# only_converter.net
KiCad netlist of a schematic drawn in Altium Designer
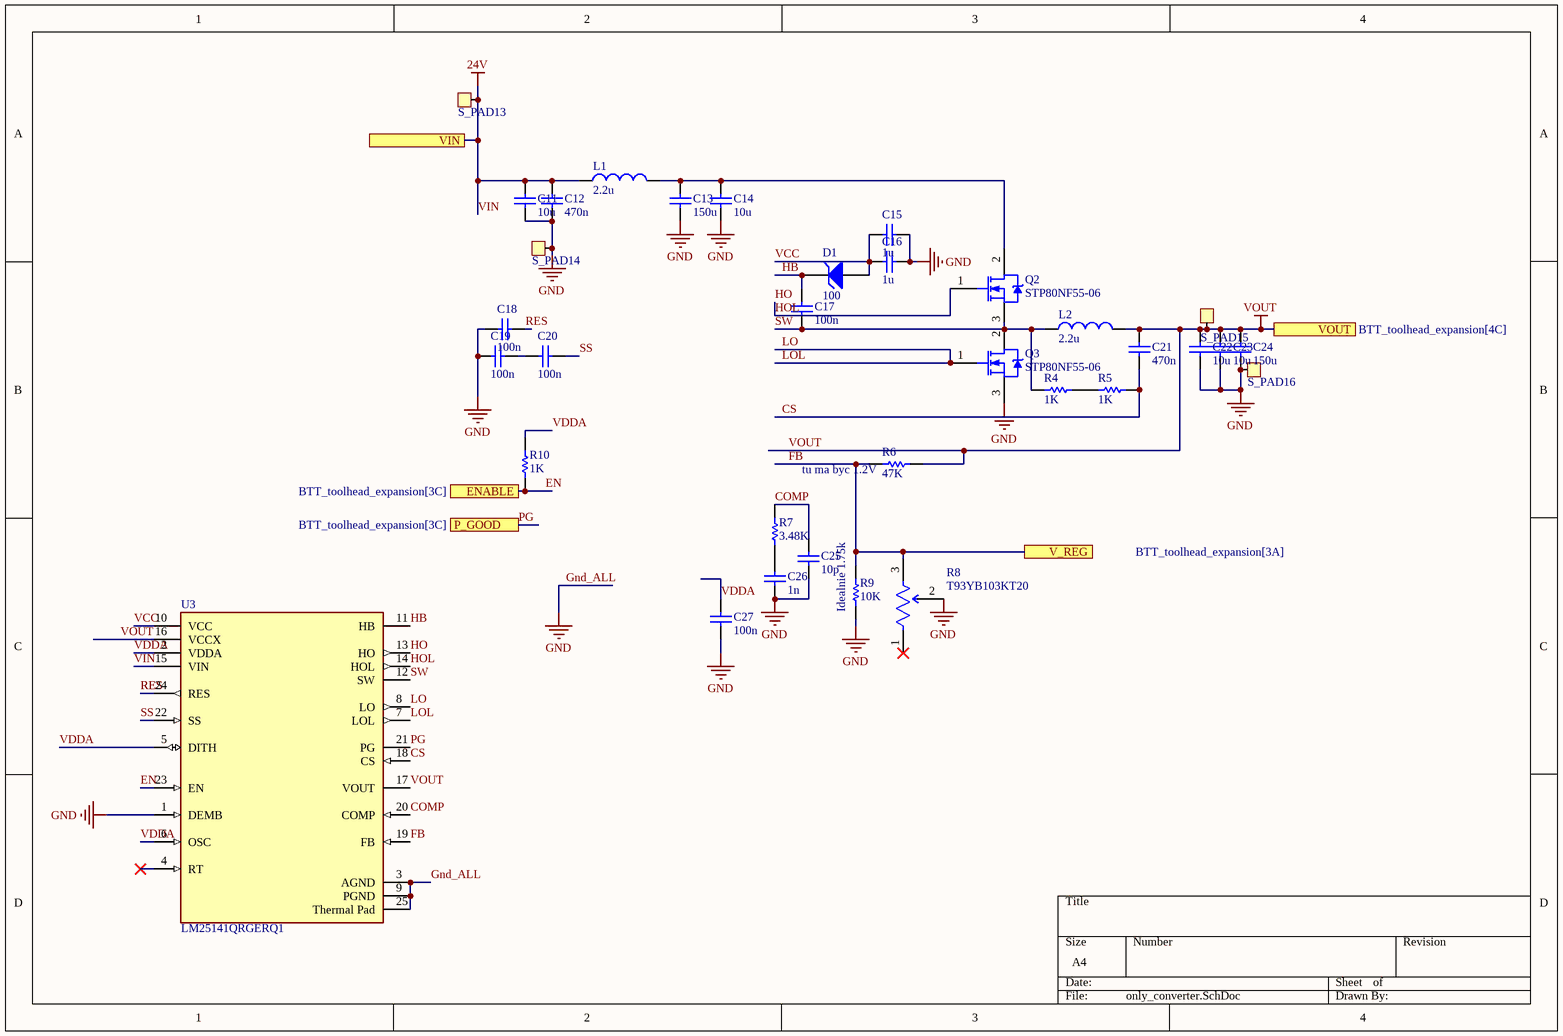
[diagram p0: only_converter.SchDoc]

(export (version "E")
  (design (tool "Eeschema 10.0.6"))
  (components
    (comp (ref "C11")
      (value "10u")
      (footprint "CAP FILM 0805")
      (description "Daj tu ten wiekszy 0805 dzbanie")
      (fields (field (name "Comment") "Capacitor"))
      (libsource (lib "Simulation Generic Components") (part "Capacitor"))
    )
    (comp (ref "C12")
      (value "470n")
      (footprint "CAP FILM 0603_1608")
      (description "Capacitor")
      (libsource (lib "Simulation Generic Components") (part "Capacitor"))
    )
    (comp (ref "C13")
      (value "150u")
      (footprint "CAPAE7266X80M")
      (description "to ten duzy elektrolityczny smd")
      (fields (field (name "Comment") "Capacitor"))
      (libsource (lib "Simulation Generic Components") (part "Capacitor"))
    )
    (comp (ref "C14")
      (value "10u")
      (footprint "CAP FILM 0805")
      (description "Daj tu ten wiekszy 0805 dzbanie")
      (fields (field (name "Comment") "Capacitor"))
      (libsource (lib "Simulation Generic Components") (part "Capacitor"))
    )
    (comp (ref "C15")
      (value "1u")
      (footprint "CAP FILM 0603_1608")
      (description "Capacitor")
      (libsource (lib "Simulation Generic Components") (part "Capacitor"))
    )
    (comp (ref "C16")
      (value "1u")
      (footprint "CAP FILM 0603_1608")
      (description "Capacitor")
      (libsource (lib "Simulation Generic Components") (part "Capacitor"))
    )
    (comp (ref "C17")
      (value "100n")
      (footprint "CAP FILM 0603_1608")
      (description "Capacitor")
      (libsource (lib "Simulation Generic Components") (part "Capacitor"))
    )
    (comp (ref "C18")
      (value "100n")
      (footprint "CAP FILM 0603_1608")
      (description "Capacitor")
      (libsource (lib "Simulation Generic Components") (part "Capacitor"))
    )
    (comp (ref "C19")
      (value "100n")
      (footprint "CAP FILM 0603_1608")
      (description "Capacitor")
      (libsource (lib "Simulation Generic Components") (part "Capacitor"))
    )
    (comp (ref "C20")
      (value "100n")
      (footprint "CAP FILM 0603_1608")
      (description "Capacitor")
      (libsource (lib "Simulation Generic Components") (part "Capacitor"))
    )
    (comp (ref "C21")
      (value "470n")
      (footprint "CAP FILM 0603_1608")
      (description "Capacitor")
      (libsource (lib "Simulation Generic Components") (part "Capacitor"))
    )
    (comp (ref "C22")
      (value "10u")
      (footprint "CAP FILM 0603_1608")
      (description "Daj tu ten wiekszy 0805 dzbanie")
      (fields (field (name "Comment") "Capacitor"))
      (libsource (lib "Simulation Generic Components") (part "Capacitor"))
    )
    (comp (ref "C23")
      (value "10u")
      (footprint "CAP FILM 0603_1608")
      (description "Daj tu ten wiekszy 0805 dzbanie")
      (fields (field (name "Comment") "Capacitor"))
      (libsource (lib "Simulation Generic Components") (part "Capacitor"))
    )
    (comp (ref "C24")
      (value "150u")
      (footprint "CAPAE7266X80M")
      (description "to ten duzy elektrolityczny smd")
      (fields (field (name "Comment") "Capacitor"))
      (libsource (lib "Simulation Generic Components") (part "Capacitor"))
    )
    (comp (ref "C25")
      (value "10p")
      (footprint "CAP FILM 0603_1608")
      (description "Capacitor")
      (libsource (lib "Simulation Generic Components") (part "Capacitor"))
    )
    (comp (ref "C26")
      (value "1n")
      (footprint "CAP FILM 0603_1608")
      (description "Capacitor")
      (libsource (lib "Simulation Generic Components") (part "Capacitor"))
    )
    (comp (ref "C27")
      (value "100n")
      (footprint "CAP FILM 0603_1608")
      (description "Capacitor")
      (libsource (lib "Simulation Generic Components") (part "Capacitor"))
    )
    (comp (ref "D1")
      (value "Zener Diode")
      (footprint "SODFL375X135-2N")
      (fields (field (name "BV") "100"))
      (libsource (lib "Simulation Generic Components") (part "Zener Diode"))
    )
    (comp (ref "L1")
      (value "2.2u")
      (footprint "INDP135128X65N")
      (description "Inductor")
      (libsource (lib "Simulation Generic Components") (part "Inductor"))
    )
    (comp (ref "L2")
      (value "2.2u")
      (footprint "INDP135128X65N")
      (description "Inductor")
      (libsource (lib "Simulation Generic Components") (part "Inductor"))
    )
    (comp (ref "Q2")
      (value "STP80NF55-06")
      (footprint "STM-TO-220A-3")
      (fields (field (name "MANUFACTURER") "STMicroelectronics"))
      (libsource (lib "Altium Content Vault") (part "NEMOS-GDS-3_B"))
    )
    (comp (ref "Q3")
      (value "STP80NF55-06")
      (footprint "STM-TO-220A-3")
      (fields (field (name "MANUFACTURER") "STMicroelectronics"))
      (libsource (lib "Altium Content Vault") (part "NEMOS-GDS-3_B"))
    )
    (comp (ref "R4")
      (value "1K")
      (footprint "RES 0603_1608")
      (description "Resistor")
      (libsource (lib "Simulation Generic Components") (part "Resistor"))
    )
    (comp (ref "R5")
      (value "1K")
      (footprint "RES 0603_1608")
      (description "Resistor")
      (libsource (lib "Simulation Generic Components") (part "Resistor"))
    )
    (comp (ref "R6")
      (value "47K")
      (footprint "RES 0603_1608")
      (description "Resistor")
      (libsource (lib "Simulation Generic Components") (part "Resistor"))
    )
    (comp (ref "R7")
      (value "3.48K")
      (footprint "RES 0603_1608")
      (description "Resistor")
      (libsource (lib "Simulation Generic Components") (part "Resistor"))
    )
    (comp (ref "R8")
      (value "T93YB103KT20")
      (footprint "FP-T93YB-MFG")
      (description "T93YB103KT20 Resistor Trimmer, Cermet, 10 kOhm, ± 10%, 500 mW, 23 Turn, Multi Turn, Through Hole")
      (fields (field (name "TOLERANCE") "10%"))
      (libsource (lib "Altium Content Vault") (part "af6d6fb613c1f66b9b47f3e4c9350cb"))
    )
    (comp (ref "R9")
      (value "10K")
      (footprint "RES 0603_1608")
      (description "Resistor")
      (libsource (lib "Simulation Generic Components") (part "Resistor"))
    )
    (comp (ref "R10")
      (value "1K")
      (footprint "RES 0603_1608 RF")
      (description "Resistor")
      (libsource (lib "Simulation Generic Components") (part "Resistor"))
    )
    (comp (ref "S_PAD13")
      (value "SOLDER_PAD")
      (footprint "POWER_PAD")
      (libsource (lib "") (part "SOLDER_PAD_1"))
    )
    (comp (ref "S_PAD14")
      (value "SOLDER_PAD")
      (footprint "POWER_PAD")
      (libsource (lib "") (part "SOLDER_PAD_2"))
    )
    (comp (ref "S_PAD15")
      (value "SOLDER_PAD")
      (footprint "POWER_PAD")
      (libsource (lib "") (part "SOLDER_PAD_3"))
    )
    (comp (ref "S_PAD16")
      (value "SOLDER_PAD")
      (footprint "POWER_PAD")
      (libsource (lib "solderpad") (part "SOLDER_PAD"))
    )
    (comp (ref "U3")
      (value "LM25141QRGERQ1")
      (footprint "FP-RGE0024J-IPC_A")
      (description "AUTOMOTIVE, 2.2MHZ, LOW IQ SYNCH")
      (libsource (lib "Altium Content Vault") (part "c442b2b45abbae5fb835a6b35668121"))
    )
  )
  (nets
    (net (code "1") (name "/COMP") (class "Default")
      (node (ref "C25") (pin "2") (pinfunction "2_2") (pintype "passive"))
      (node (ref "R7") (pin "2") (pinfunction "2_2") (pintype "passive"))
      (node (ref "U3") (pin "20") (pinfunction "COMP_20") (pintype "input"))
    )
    (net (code "2") (name "/CS") (class "Default")
      (node (ref "C21") (pin "1") (pinfunction "1_1") (pintype "passive"))
      (node (ref "R5") (pin "2") (pinfunction "2_2") (pintype "passive"))
      (node (ref "U3") (pin "18") (pinfunction "CS_18") (pintype "input"))
    )
    (net (code "3") (name "/EN") (class "Default")
      (node (ref "R10") (pin "1") (pinfunction "1_1") (pintype "passive"))
      (node (ref "U3") (pin "23") (pinfunction "EN_23") (pintype "input"))
    )
    (net (code "4") (name "/FB") (class "Default")
      (node (ref "R6") (pin "1") (pinfunction "1_1") (pintype "passive"))
      (node (ref "R8") (pin "3") (pinfunction "c_3") (pintype "passive"))
      (node (ref "R9") (pin "2") (pinfunction "2_2") (pintype "passive"))
      (node (ref "U3") (pin "19") (pinfunction "FB_19") (pintype "input"))
    )
    (net (code "5") (name "/HB") (class "Default")
      (node (ref "C17") (pin "2") (pinfunction "2_2") (pintype "passive"))
      (node (ref "D1") (pin "2") (pinfunction "K_2") (pintype "passive"))
      (node (ref "U3") (pin "11") (pinfunction "HB_11") (pintype "power_in"))
    )
    (net (code "6") (name "/HO") (class "Default")
      (node (ref "Q2") (pin "1") (pinfunction "G_1") (pintype "passive"))
      (node (ref "U3") (pin "13") (pinfunction "HO_13") (pintype "output"))
      (node (ref "U3") (pin "14") (pinfunction "HOL_14") (pintype "output"))
    )
    (net (code "7") (name "/LO") (class "Default")
      (node (ref "Q3") (pin "1") (pinfunction "G_1") (pintype "passive"))
      (node (ref "U3") (pin "7") (pinfunction "LOL_7") (pintype "output"))
      (node (ref "U3") (pin "8") (pinfunction "LO_8") (pintype "output"))
    )
    (net (code "8") (name "/PG") (class "Default")
      (node (ref "U3") (pin "21") (pinfunction "PG_21") (pintype "open_collector"))
    )
    (net (code "9") (name "/RES") (class "Default")
      (node (ref "C18") (pin "2") (pinfunction "2_2") (pintype "passive"))
      (node (ref "U3") (pin "24") (pinfunction "RES_24") (pintype "output"))
    )
    (net (code "10") (name "/SS") (class "Default")
      (node (ref "C20") (pin "2") (pinfunction "2_2") (pintype "passive"))
      (node (ref "U3") (pin "22") (pinfunction "SS_22") (pintype "input"))
    )
    (net (code "11") (name "/SW") (class "Default")
      (node (ref "C17") (pin "1") (pinfunction "1_1") (pintype "passive"))
      (node (ref "L2") (pin "1") (pinfunction "1_1") (pintype "passive"))
      (node (ref "Q2") (pin "3") (pinfunction "S_3") (pintype "passive"))
      (node (ref "Q3") (pin "2") (pinfunction "D_2") (pintype "passive"))
      (node (ref "R4") (pin "1") (pinfunction "1_1") (pintype "passive"))
      (node (ref "U3") (pin "12") (pinfunction "SW_12") (pintype "power_in"))
    )
    (net (code "12") (name "/VCC") (class "Default")
      (node (ref "C15") (pin "2") (pinfunction "2_2") (pintype "passive"))
      (node (ref "C16") (pin "2") (pinfunction "2_2") (pintype "passive"))
      (node (ref "D1") (pin "1") (pinfunction "A_1") (pintype "passive"))
      (node (ref "U3") (pin "10") (pinfunction "VCC_10") (pintype "power_in"))
    )
    (net (code "13") (name "/VDDA") (class "Default")
      (node (ref "C27") (pin "2") (pinfunction "2_2") (pintype "passive"))
      (node (ref "R10") (pin "2") (pinfunction "2_2") (pintype "passive"))
      (node (ref "U3") (pin "2") (pinfunction "VDDA_2") (pintype "power_in"))
      (node (ref "U3") (pin "5") (pinfunction "DITH_5") (pintype "bidirectional"))
      (node (ref "U3") (pin "6") (pinfunction "OSC_6") (pintype "input"))
    )
    (net (code "14") (name "24V") (class "Default")
      (node (ref "C11") (pin "2") (pinfunction "2_2") (pintype "passive"))
      (node (ref "C12") (pin "2") (pinfunction "2_2") (pintype "passive"))
      (node (ref "L1") (pin "1") (pinfunction "1_1") (pintype "passive"))
      (node (ref "S_PAD13") (pin "1") (pinfunction "0_1") (pintype "passive"))
      (node (ref "U3") (pin "15") (pinfunction "VIN_15") (pintype "power_in"))
    )
    (net (code "15") (name "GND") (class "Default")
      (node (ref "C11") (pin "1") (pinfunction "1_1") (pintype "passive"))
      (node (ref "C12") (pin "1") (pinfunction "1_1") (pintype "passive"))
      (node (ref "C13") (pin "1") (pinfunction "1_1") (pintype "passive"))
      (node (ref "C14") (pin "1") (pinfunction "1_1") (pintype "passive"))
      (node (ref "C15") (pin "1") (pinfunction "1_1") (pintype "passive"))
      (node (ref "C16") (pin "1") (pinfunction "1_1") (pintype "passive"))
      (node (ref "C18") (pin "1") (pinfunction "1_1") (pintype "passive"))
      (node (ref "C19") (pin "1") (pinfunction "1_1") (pintype "passive"))
      (node (ref "C22") (pin "1") (pinfunction "1_1") (pintype "passive"))
      (node (ref "C23") (pin "1") (pinfunction "1_1") (pintype "passive"))
      (node (ref "C24") (pin "1") (pinfunction "1_1") (pintype "passive"))
      (node (ref "C25") (pin "1") (pinfunction "1_1") (pintype "passive"))
      (node (ref "C26") (pin "1") (pinfunction "1_1") (pintype "passive"))
      (node (ref "C27") (pin "1") (pinfunction "1_1") (pintype "passive"))
      (node (ref "Q3") (pin "3") (pinfunction "S_3") (pintype "passive"))
      (node (ref "R8") (pin "2") (pinfunction "b_2") (pintype "passive"))
      (node (ref "R9") (pin "1") (pinfunction "1_1") (pintype "passive"))
      (node (ref "S_PAD14") (pin "1") (pinfunction "0_1") (pintype "passive"))
      (node (ref "S_PAD16") (pin "1") (pinfunction "0_1") (pintype "passive"))
      (node (ref "U3") (pin "1") (pinfunction "DEMB_1") (pintype "input"))
      (node (ref "U3") (pin "25") (pinfunction "Thermal_Pad_25") (pintype "power_in"))
      (node (ref "U3") (pin "3") (pinfunction "AGND_3") (pintype "power_in"))
      (node (ref "U3") (pin "9") (pinfunction "PGND_9") (pintype "power_in"))
    )
    (net (code "16") (name "Net-(C19-Pad2)") (class "Default")
      (node (ref "C19") (pin "2") (pinfunction "2_2") (pintype "passive"))
      (node (ref "C20") (pin "1") (pinfunction "1_1") (pintype "passive"))
    )
    (net (code "17") (name "Net-(C26-Pad2)") (class "Default")
      (node (ref "C26") (pin "2") (pinfunction "2_2") (pintype "passive"))
      (node (ref "R7") (pin "1") (pinfunction "1_1") (pintype "passive"))
    )
    (net (code "18") (name "Net-(Q2-D)") (class "Default")
      (node (ref "C13") (pin "2") (pinfunction "2_2") (pintype "passive"))
      (node (ref "C14") (pin "2") (pinfunction "2_2") (pintype "passive"))
      (node (ref "L1") (pin "2") (pinfunction "2_2") (pintype "passive"))
      (node (ref "Q2") (pin "2") (pinfunction "D_2") (pintype "passive"))
    )
    (net (code "19") (name "Net-(R4-Pad2)") (class "Default")
      (node (ref "R4") (pin "2") (pinfunction "2_2") (pintype "passive"))
      (node (ref "R5") (pin "1") (pinfunction "1_1") (pintype "passive"))
    )
    (net (code "20") (name "VOUT") (class "Default")
      (node (ref "C21") (pin "2") (pinfunction "2_2") (pintype "passive"))
      (node (ref "C22") (pin "2") (pinfunction "2_2") (pintype "passive"))
      (node (ref "C23") (pin "2") (pinfunction "2_2") (pintype "passive"))
      (node (ref "C24") (pin "2") (pinfunction "2_2") (pintype "passive"))
      (node (ref "L2") (pin "2") (pinfunction "2_2") (pintype "passive"))
      (node (ref "R6") (pin "2") (pinfunction "2_2") (pintype "passive"))
      (node (ref "S_PAD15") (pin "1") (pinfunction "0_1") (pintype "passive"))
      (node (ref "U3") (pin "16") (pinfunction "VCCX_16") (pintype "power_in"))
      (node (ref "U3") (pin "17") (pinfunction "VOUT_17") (pintype "power_in"))
    )
    (net (code "21") (name "unconnected-(R8-a-Pad1)") (class "Default")
      (node (ref "R8") (pin "1") (pinfunction "a_1") (pintype "passive+no_connect"))
    )
    (net (code "22") (name "unconnected-(U3-RT-Pad4)") (class "Default")
      (node (ref "U3") (pin "4") (pinfunction "RT_4") (pintype "input+no_connect"))
    )
  )
)
